# Schematic.net
KiCad netlist of a schematic drawn in EAGLE
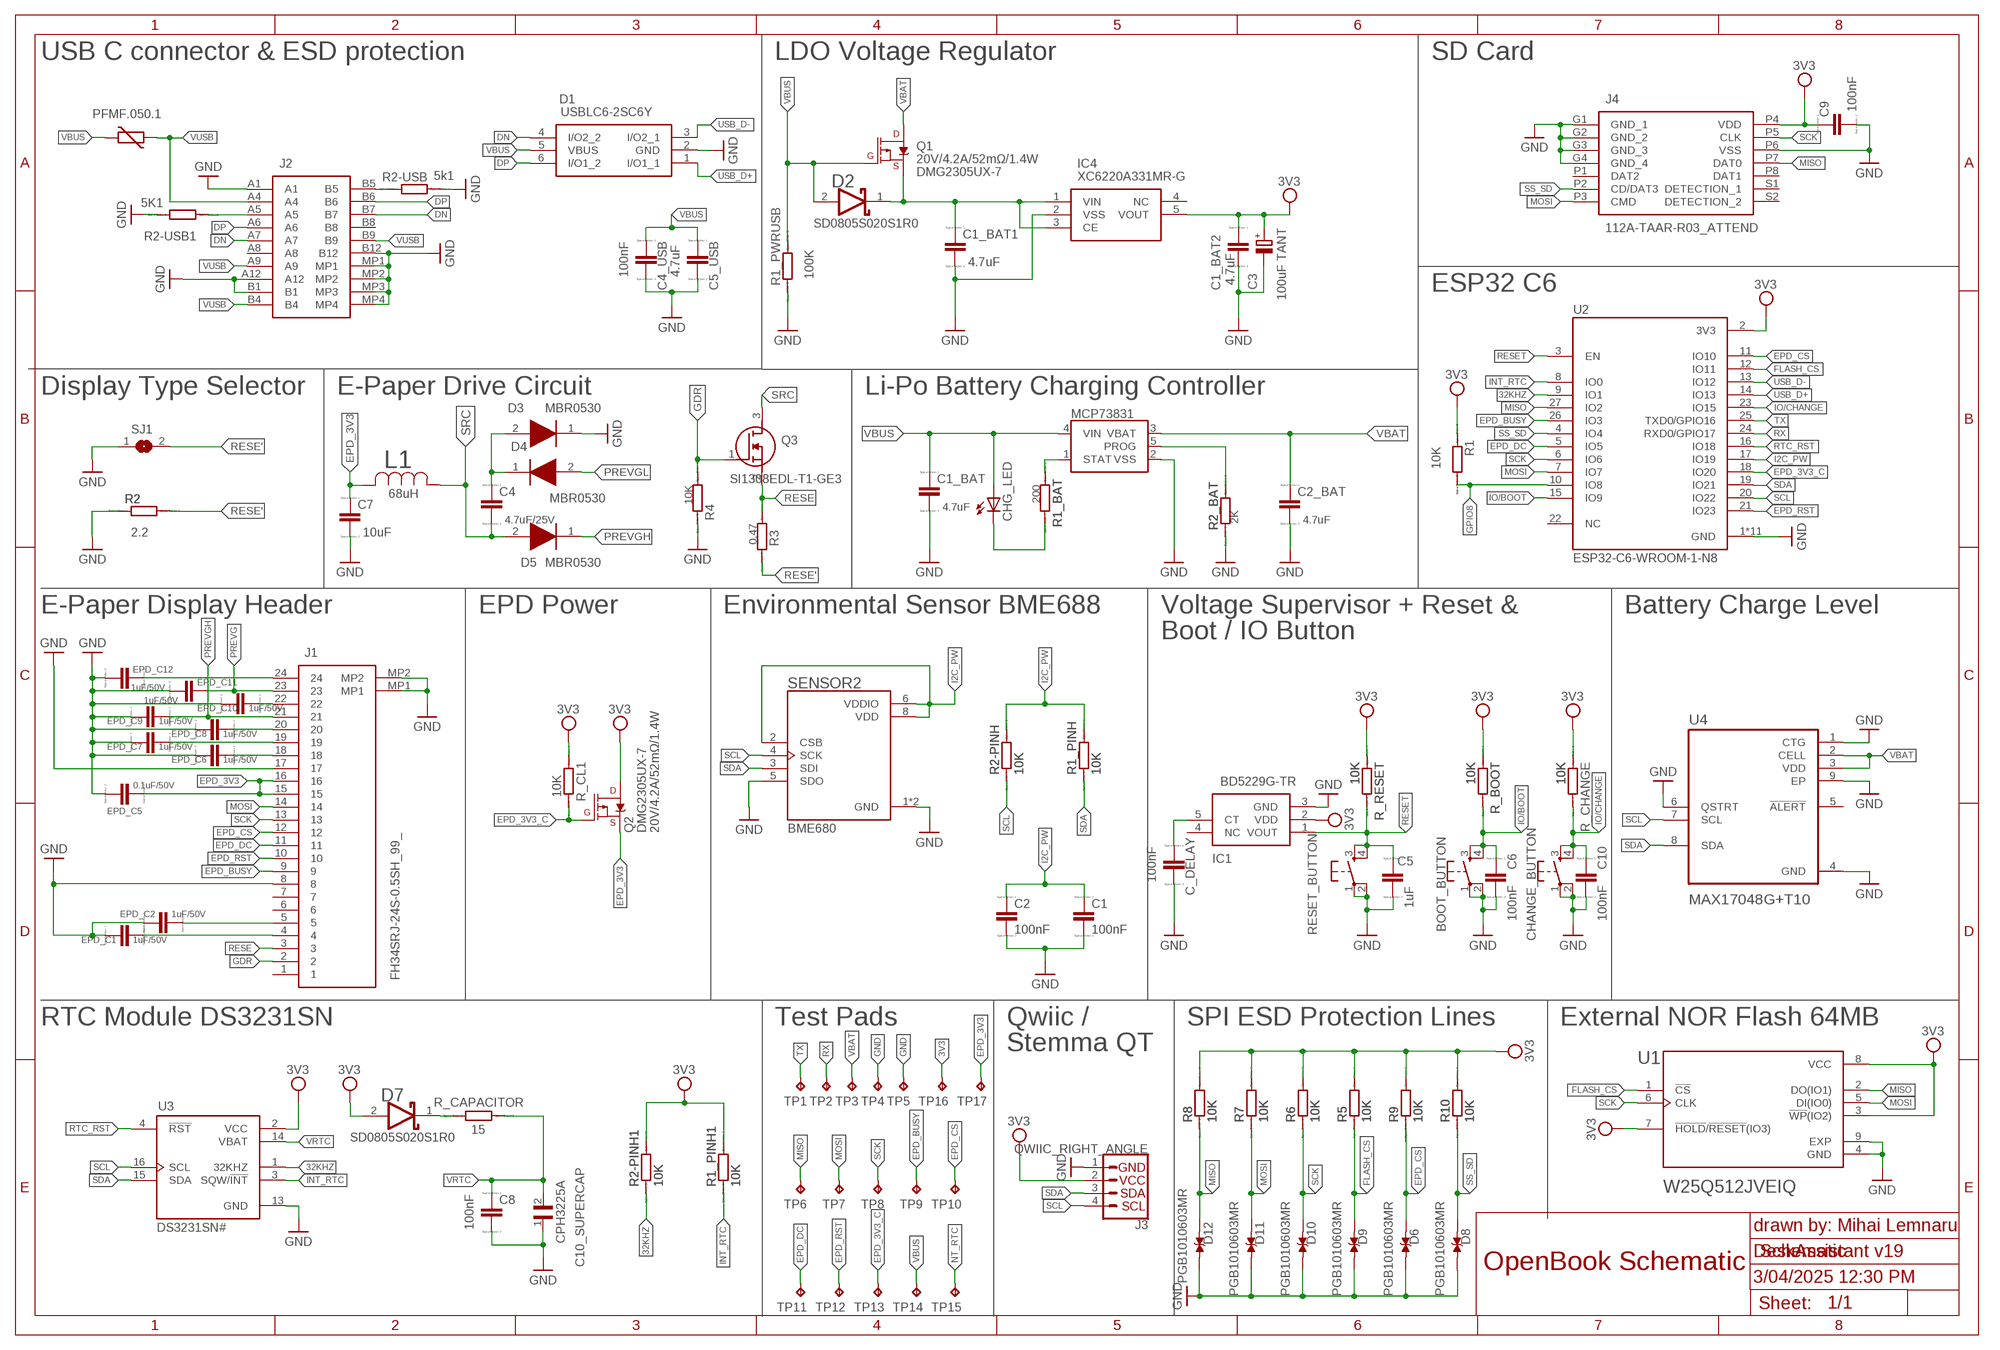
[diagram p0: schematic, sheet 1]

(export (version "E")
  (design (tool "Eeschema 10.0.6"))
  (components
    (comp (ref "5K1")
      (value "ESP32_WROVER_EAGLE-LTSPICE_RR0402")
      (footprint "eagle-import:ESP32_WROVER_EAGLE-LTSPICE_R0402")
      (libsource (lib "eagle-import") (part "ESP32_WROVER_EAGLE-LTSPICE_RR0402"))
    )
    (comp (ref "BOOT_BUTTON")
      (value "BUTTON_CUSYOMV1")
      (footprint "eagle-import:MYBUTTON")
      (libsource (lib "eagle-import") (part "BUTTON_CUSYOMV1"))
    )
    (comp (ref "C1")
      (value "100nF")
      (footprint "eagle-import:EAGLE-LTSPICE_C0402")
      (libsource (lib "eagle-import") (part "EAGLE-LTSPICE_CC0402"))
    )
    (comp (ref "C1_BAT")
      (value "EAGLE-LTSPICE_CC0402")
      (footprint "eagle-import:EAGLE-LTSPICE_C0402")
      (fields (field (name "C4_BAT") "4.7uF"))
      (libsource (lib "eagle-import") (part "EAGLE-LTSPICE_CC0402"))
    )
    (comp (ref "C1_BAT1")
      (value "EAGLE-LTSPICE_CC0402")
      (footprint "eagle-import:EAGLE-LTSPICE_C0402")
      (fields (field (name "C1_BAT1") "4.7uF"))
      (libsource (lib "eagle-import") (part "EAGLE-LTSPICE_CC0402"))
    )
    (comp (ref "C1_BAT2")
      (value "EAGLE-LTSPICE_CC0402")
      (footprint "eagle-import:EAGLE-LTSPICE_C0402")
      (fields (field (name "C1_BAT2") "4.7uF"))
      (libsource (lib "eagle-import") (part "EAGLE-LTSPICE_CC0402"))
    )
    (comp (ref "C2")
      (value "100nF")
      (footprint "eagle-import:EAGLE-LTSPICE_C0402")
      (libsource (lib "eagle-import") (part "EAGLE-LTSPICE_CC0402"))
    )
    (comp (ref "C2_BAT")
      (value "EAGLE-LTSPICE_CC0402")
      (footprint "eagle-import:EAGLE-LTSPICE_C0402")
      (fields (field (name "C2_BAT") "4.7uF"))
      (libsource (lib "eagle-import") (part "EAGLE-LTSPICE_CC0402"))
    )
    (comp (ref "C3")
      (value "RCL_CPOL-EUCT3528")
      (footprint "eagle-import:RCL_CT3528")
      (fields (field (name "C3") "100uF TANT"))
      (libsource (lib "eagle-import") (part "RCL_CPOL-EUCT3528"))
    )
    (comp (ref "C4")
      (value "ESP32_WROVER_EAGLE-LTSPICE_CC0402")
      (footprint "eagle-import:ESP32_WROVER_EAGLE-LTSPICE_C0402")
      (fields (field (name "C4") "4.7uF/25V"))
      (libsource (lib "eagle-import") (part "ESP32_WROVER_EAGLE-LTSPICE_CC0402"))
    )
    (comp (ref "C4_USB")
      (value "100nF")
      (footprint "eagle-import:EAGLE-LTSPICE_C0402")
      (fields (field (name "C4_USB") "100nF"))
      (libsource (lib "eagle-import") (part "EAGLE-LTSPICE_CC0402"))
    )
    (comp (ref "C5")
      (value "1uF")
      (footprint "eagle-import:EAGLE-LTSPICE_C0402")
      (libsource (lib "eagle-import") (part "EAGLE-LTSPICE_CC0402"))
    )
    (comp (ref "C5_USB")
      (value "4.7uF")
      (footprint "eagle-import:EAGLE-LTSPICE_C0402")
      (fields (field (name "C5_USB") "4.7uF"))
      (libsource (lib "eagle-import") (part "EAGLE-LTSPICE_CC0402"))
    )
    (comp (ref "C6")
      (value "100nF")
      (footprint "eagle-import:EAGLE-LTSPICE_C0402")
      (libsource (lib "eagle-import") (part "EAGLE-LTSPICE_CC0402"))
    )
    (comp (ref "C7")
      (value "ESP32_WROVER_EAGLE-LTSPICE_CC0402")
      (footprint "eagle-import:ESP32_WROVER_EAGLE-LTSPICE_C0402")
      (fields (field (name "C7") "10uF"))
      (libsource (lib "eagle-import") (part "ESP32_WROVER_EAGLE-LTSPICE_CC0402"))
    )
    (comp (ref "C8")
      (value "100nF")
      (footprint "eagle-import:EAGLE-LTSPICE_C0402")
      (libsource (lib "eagle-import") (part "EAGLE-LTSPICE_CC0402"))
    )
    (comp (ref "C9")
      (value "EAGLE-LTSPICE_CC0402")
      (footprint "eagle-import:EAGLE-LTSPICE_C0402")
      (fields (field (name "C9") "100nF"))
      (libsource (lib "eagle-import") (part "EAGLE-LTSPICE_CC0402"))
    )
    (comp (ref "C10")
      (value "100nF")
      (footprint "eagle-import:EAGLE-LTSPICE_C0402")
      (libsource (lib "eagle-import") (part "EAGLE-LTSPICE_CC0402"))
    )
    (comp (ref "C10_SUPERCAP")
      (value "CPH3225A")
      (footprint "eagle-import:CAPCP3225X100N")
      (fields (field (name "MF") "Seiko Instruments"))
      (libsource (lib "eagle-import") (part "CPH3225A"))
    )
    (comp (ref "CHANGE_BUTTON")
      (value "BUTTON_CUSYOMV1")
      (footprint "eagle-import:MYBUTTON")
      (libsource (lib "eagle-import") (part "BUTTON_CUSYOMV1"))
    )
    (comp (ref "CHG_LED")
      (value "ADAFRUIT_LEDCHIP-LED0603")
      (footprint "eagle-import:ADAFRUIT_CHIP-LED0603")
      (libsource (lib "eagle-import") (part "ADAFRUIT_LEDCHIP-LED0603"))
    )
    (comp (ref "C_DELAY")
      (value "100nF")
      (footprint "eagle-import:EAGLE-LTSPICE_C0402")
      (libsource (lib "eagle-import") (part "EAGLE-LTSPICE_CC0402"))
    )
    (comp (ref "D1")
      (value "USBLC6-2SC6Y")
      (footprint "eagle-import:SOT95P280X145-6N")
      (fields (field (name "MF") "STMicroelectronics"))
      (libsource (lib "eagle-import") (part "USBLC6-2SC6Y"))
    )
    (comp (ref "D2")
      (value "ESP32_WROVER_AVX---SD0805S020S1R0_AVX_SD0805S020S1R0_0_0AVX_SD0805S020S1R0_0_0")
      (footprint "eagle-import:ESP32_WROVER_AVX---SD0805S020S1R0_AVX_SD0805S020S1R0_0")
      (fields
        (field (name "DIGIKEY_PART_NUMBER") "478-7800-1-ND")
        (field (name "MF") "AVX")
        (field (name "MOUSER_PART_NUMBER") "581-SD0805S020S1R0")
      )
      (libsource (lib "eagle-import") (part "ESP32_WROVER_AVX---SD0805S020S1R0_AVX_SD0805S020S1R0_0_0AVX_SD0805S020S1R0_0_0"))
    )
    (comp (ref "D3")
      (value "MBR0530")
      (footprint "eagle-import:SOD3716X135N")
      (fields (field (name "MF") "ON Semiconductor"))
      (libsource (lib "eagle-import") (part "MBR0530"))
    )
    (comp (ref "D4")
      (value "MBR0530")
      (footprint "eagle-import:SOD3716X135N")
      (fields (field (name "MF") "ON Semiconductor"))
      (libsource (lib "eagle-import") (part "MBR0530"))
    )
    (comp (ref "D5")
      (value "MBR0530")
      (footprint "eagle-import:SOD3716X135N")
      (fields (field (name "MF") "ON Semiconductor"))
      (libsource (lib "eagle-import") (part "MBR0530"))
    )
    (comp (ref "D6")
      (value "PGB1010603MR")
      (footprint "eagle-import:DIOC1608X36N")
      (fields (field (name "MF") "Littelfuse Inc."))
      (libsource (lib "eagle-import") (part "PGB1010603MR"))
    )
    (comp (ref "D7")
      (value "ESP32_WROVER_AVX---SD0805S020S1R0_AVX_SD0805S020S1R0_0_0AVX_SD0805S020S1R0_0_0")
      (footprint "eagle-import:ESP32_WROVER_AVX---SD0805S020S1R0_AVX_SD0805S020S1R0_0")
      (fields
        (field (name "DIGIKEY_PART_NUMBER") "478-7800-1-ND")
        (field (name "MF") "AVX")
        (field (name "MOUSER_PART_NUMBER") "581-SD0805S020S1R0")
      )
      (libsource (lib "eagle-import") (part "ESP32_WROVER_AVX---SD0805S020S1R0_AVX_SD0805S020S1R0_0_0AVX_SD0805S020S1R0_0_0"))
    )
    (comp (ref "D8")
      (value "PGB1010603MR")
      (footprint "eagle-import:DIOC1608X36N")
      (fields (field (name "MF") "Littelfuse Inc."))
      (libsource (lib "eagle-import") (part "PGB1010603MR"))
    )
    (comp (ref "D9")
      (value "PGB1010603MR")
      (footprint "eagle-import:DIOC1608X36N")
      (fields (field (name "MF") "Littelfuse Inc."))
      (libsource (lib "eagle-import") (part "PGB1010603MR"))
    )
    (comp (ref "D10")
      (value "PGB1010603MR")
      (footprint "eagle-import:DIOC1608X36N")
      (fields (field (name "MF") "Littelfuse Inc."))
      (libsource (lib "eagle-import") (part "PGB1010603MR"))
    )
    (comp (ref "D11")
      (value "PGB1010603MR")
      (footprint "eagle-import:DIOC1608X36N")
      (fields (field (name "MF") "Littelfuse Inc."))
      (libsource (lib "eagle-import") (part "PGB1010603MR"))
    )
    (comp (ref "D12")
      (value "PGB1010603MR")
      (footprint "eagle-import:DIOC1608X36N")
      (fields (field (name "MF") "Littelfuse Inc."))
      (libsource (lib "eagle-import") (part "PGB1010603MR"))
    )
    (comp (ref "EPD_C1")
      (value "1uF/50V")
      (footprint "eagle-import:ESP32_WROVER_EAGLE-LTSPICE_C0402")
      (libsource (lib "eagle-import") (part "ESP32_WROVER_EAGLE-LTSPICE_CC0402"))
    )
    (comp (ref "EPD_C2")
      (value "1uF/50V")
      (footprint "eagle-import:ESP32_WROVER_EAGLE-LTSPICE_C0402")
      (libsource (lib "eagle-import") (part "ESP32_WROVER_EAGLE-LTSPICE_CC0402"))
    )
    (comp (ref "EPD_C5")
      (value "0.1uF/50V")
      (footprint "eagle-import:EAGLE-LTSPICE_C0402")
      (libsource (lib "eagle-import") (part "EAGLE-LTSPICE_CC0402"))
    )
    (comp (ref "EPD_C6")
      (value "1uF/50V")
      (footprint "eagle-import:EAGLE-LTSPICE_C0402")
      (libsource (lib "eagle-import") (part "EAGLE-LTSPICE_CC0402"))
    )
    (comp (ref "EPD_C7")
      (value "1uF/50V")
      (footprint "eagle-import:EAGLE-LTSPICE_C0402")
      (fields (field (name "EPD_C7") "1uF/50V"))
      (libsource (lib "eagle-import") (part "EAGLE-LTSPICE_CC0402"))
    )
    (comp (ref "EPD_C8")
      (value "1uF/50V")
      (footprint "eagle-import:EAGLE-LTSPICE_C0402")
      (fields (field (name "EPD_C8") "1uF/50V"))
      (libsource (lib "eagle-import") (part "EAGLE-LTSPICE_CC0402"))
    )
    (comp (ref "EPD_C9")
      (value "1uF/50V")
      (footprint "eagle-import:EAGLE-LTSPICE_C0402")
      (fields (field (name "EPD_C9") "1uF/50V"))
      (libsource (lib "eagle-import") (part "EAGLE-LTSPICE_CC0402"))
    )
    (comp (ref "EPD_C10")
      (value "1uF/50V")
      (footprint "eagle-import:EAGLE-LTSPICE_C0402")
      (fields (field (name "EPD_C10") "1uF/50V"))
      (libsource (lib "eagle-import") (part "EAGLE-LTSPICE_CC0402"))
    )
    (comp (ref "EPD_C11")
      (value "EAGLE-LTSPICE_CC0402")
      (footprint "eagle-import:EAGLE-LTSPICE_C0402")
      (fields (field (name "EPD_C11") "1uF/50V"))
      (libsource (lib "eagle-import") (part "EAGLE-LTSPICE_CC0402"))
    )
    (comp (ref "EPD_C12")
      (value "EAGLE-LTSPICE_CC0402")
      (footprint "eagle-import:EAGLE-LTSPICE_C0402")
      (fields (field (name "EPD_C12") "1uF/50V"))
      (libsource (lib "eagle-import") (part "EAGLE-LTSPICE_CC0402"))
    )
    (comp (ref "IC1")
      (value "BD5229G-TR")
      (footprint "eagle-import:SOT95P280X125-5N")
      (fields (field (name "MOUSER_PART_NUMBER") "755-BD5229G-TR"))
      (libsource (lib "eagle-import") (part "BD5229G-TR"))
    )
    (comp (ref "IC4")
      (value "XC6220A331MR-G")
      (footprint "eagle-import:SOT95P280X120-5N")
      (fields (field (name "MOUSER_PART_NUMBER") "865-XC6220A331MR-G"))
      (libsource (lib "eagle-import") (part "XC6220A331MR-G"))
    )
    (comp (ref "J1")
      (value "FH34SRJ-24S-0.5SH_99_")
      (footprint "eagle-import:FH34SRJ24S05SH99")
      (fields
        (field (name "MANUFACTURER_PART_NUMBER") "FH34SRJ-24S-0.5SH(99)")
        (field (name "MOUSER_PART_NUMBER") "798-FH34SRJ24S05SH99")
      )
      (libsource (lib "eagle-import") (part "FH34SRJ-24S-0.5SH_99_"))
    )
    (comp (ref "J2")
      (value "SAMACSYS_PARTS_USB4110-GF-A")
      (footprint "eagle-import:SAMACSYS_PARTS_USB4110GFA")
      (fields
        (field (name "MANUFACTURER_PART_NUMBER") "USB4110-GF-A")
        (field (name "MOUSER_PART_NUMBER") "640-USB4110-GF-A")
      )
      (libsource (lib "eagle-import") (part "SAMACSYS_PARTS_USB4110-GF-A"))
    )
    (comp (ref "J3")
      (value "QWIIC_RIGHT_ANGLE")
      (footprint "eagle-import:JST04_1MM_RA")
      (libsource (lib "eagle-import") (part "QWIIC_CONNECTORJS-1MM"))
    )
    (comp (ref "J4")
      (value "112A-TAAR-R03_ATTEND")
      (footprint "eagle-import:112ATAARR03ATTEND")
      (fields (field (name "MANUFACTURER_PART_NUMBER") "112A-TAAR-R03 ATTEND"))
      (libsource (lib "eagle-import") (part "112A-TAAR-R03_ATTEND"))
    )
    (comp (ref "L1")
      (value "744043680IND_4828-WE-TPC_WRE")
      (footprint "eagle-import:IND_4828-WE-TPC_WRE")
      (fields
        (field (name "MANUFACTURER_PART_NUMBER") "744043680")
        (field (name "L1") "68uH")
        (field (name "COPYRIGHT") "Copyright (C) 2024 Ultra Librarian. All rights reserved.")
      )
      (libsource (lib "eagle-import") (part "744043680IND_4828-WE-TPC_WRE"))
    )
    (comp (ref "MCP73831")
      (value "ESP32_WROVER_SPARKFUN-IC-POWER_MCP73831")
      (footprint "eagle-import:ESP32_WROVER_SPARKFUN-IC-POWER_SOT23-5")
      (libsource (lib "eagle-import") (part "ESP32_WROVER_SPARKFUN-IC-POWER_MCP73831"))
    )
    (comp (ref "PFMF.050.1")
      (value "ESP32C6_VARISTORCN1812")
      (footprint "eagle-import:ESP32C6_VARISTOR_CT_CN1812")
      (libsource (lib "eagle-import") (part "ESP32C6_VARISTORCN1812"))
    )
    (comp (ref "Q1")
      (value "20V/4.2A/52mΩ/1.4W")
      (footprint "eagle-import:ESP32_WROVER_SPARKFUN-DISCRETESEMI_SOT23-3")
      (libsource (lib "eagle-import") (part "ESP32_WROVER_SPARKFUN-DISCRETESEMI_MOSFET_PCH-DMG2305UX-7"))
    )
    (comp (ref "Q2")
      (value "20V/4.2A/52mΩ/1.4W")
      (footprint "eagle-import:ESP32_WROVER_SPARKFUN-DISCRETESEMI_SOT23-3")
      (libsource (lib "eagle-import") (part "ESP32_WROVER_SPARKFUN-DISCRETESEMI_MOSFET_PCH-DMG2305UX-7"))
    )
    (comp (ref "Q3")
      (value "SI1308EDL-T1-GE3")
      (footprint "eagle-import:SOT65P210X110-3N")
      (fields (field (name "MF") "Vishay Siliconix"))
      (libsource (lib "eagle-import") (part "SI1308EDL-T1-GE3"))
    )
    (comp (ref "R1")
      (value "ESP32_WROVER_EAGLE-LTSPICE_RR0402")
      (footprint "eagle-import:ESP32_WROVER_EAGLE-LTSPICE_R0402")
      (fields (field (name "R1") "10K"))
      (libsource (lib "eagle-import") (part "ESP32_WROVER_EAGLE-LTSPICE_RR0402"))
    )
    (comp (ref "R1_BAT")
      (value "ESP32_WROVER_EAGLE-LTSPICE_RR0402")
      (footprint "eagle-import:ESP32_WROVER_EAGLE-LTSPICE_R0402")
      (fields (field (name "R1_BAT") "200"))
      (libsource (lib "eagle-import") (part "ESP32_WROVER_EAGLE-LTSPICE_RR0402"))
    )
    (comp (ref "R1_PINH")
      (value "10K")
      (footprint "eagle-import:ESP32_WROVER_EAGLE-LTSPICE_R0402")
      (libsource (lib "eagle-import") (part "ESP32_WROVER_EAGLE-LTSPICE_RR0402"))
    )
    (comp (ref "R1_PINH1")
      (value "10K")
      (footprint "eagle-import:ESP32_WROVER_EAGLE-LTSPICE_R0402")
      (libsource (lib "eagle-import") (part "ESP32_WROVER_EAGLE-LTSPICE_RR0402"))
    )
    (comp (ref "R1_PWRUSB")
      (value "ESP32_WROVER_EAGLE-LTSPICE_RR0402")
      (footprint "eagle-import:ESP32_WROVER_EAGLE-LTSPICE_R0402")
      (fields (field (name "R1_PWRUSB") "100K"))
      (libsource (lib "eagle-import") (part "ESP32_WROVER_EAGLE-LTSPICE_RR0402"))
    )
    (comp (ref "R2")
      (value "ESP32_WROVER_EAGLE-LTSPICE_RR0402")
      (footprint "eagle-import:ESP32_WROVER_EAGLE-LTSPICE_R0402")
      (fields (field (name "R2") "2.2"))
      (libsource (lib "eagle-import") (part "ESP32_WROVER_EAGLE-LTSPICE_RR0402"))
    )
    (comp (ref "R2-PINH")
      (value "10K")
      (footprint "eagle-import:ESP32_WROVER_EAGLE-LTSPICE_R0402")
      (libsource (lib "eagle-import") (part "ESP32_WROVER_EAGLE-LTSPICE_RR0402"))
    )
    (comp (ref "R2-PINH1")
      (value "10K")
      (footprint "eagle-import:ESP32_WROVER_EAGLE-LTSPICE_R0402")
      (libsource (lib "eagle-import") (part "ESP32_WROVER_EAGLE-LTSPICE_RR0402"))
    )
    (comp (ref "R2-USB")
      (value "5k1")
      (footprint "eagle-import:ESP32_WROVER_EAGLE-LTSPICE_R0402")
      (libsource (lib "eagle-import") (part "ESP32_WROVER_EAGLE-LTSPICE_RR0402"))
    )
    (comp (ref "R2_BAT")
      (value "ESP32_WROVER_EAGLE-LTSPICE_RR0402")
      (footprint "eagle-import:ESP32_WROVER_EAGLE-LTSPICE_R0402")
      (fields (field (name "R2_BAT") "2K"))
      (libsource (lib "eagle-import") (part "ESP32_WROVER_EAGLE-LTSPICE_RR0402"))
    )
    (comp (ref "R3")
      (value "ESP32_WROVER_EAGLE-LTSPICE_RR0402")
      (footprint "eagle-import:ESP32_WROVER_EAGLE-LTSPICE_R0402")
      (fields (field (name "R3") "0.47"))
      (libsource (lib "eagle-import") (part "ESP32_WROVER_EAGLE-LTSPICE_RR0402"))
    )
    (comp (ref "R4")
      (value "ESP32_WROVER_EAGLE-LTSPICE_RR0402")
      (footprint "eagle-import:ESP32_WROVER_EAGLE-LTSPICE_R0402")
      (fields (field (name "R4") "10K"))
      (libsource (lib "eagle-import") (part "ESP32_WROVER_EAGLE-LTSPICE_RR0402"))
    )
    (comp (ref "R5")
      (value "10K")
      (footprint "eagle-import:ESP32_WROVER_EAGLE-LTSPICE_R0402")
      (libsource (lib "eagle-import") (part "ESP32_WROVER_EAGLE-LTSPICE_RR0402"))
    )
    (comp (ref "R6")
      (value "10K")
      (footprint "eagle-import:ESP32_WROVER_EAGLE-LTSPICE_R0402")
      (libsource (lib "eagle-import") (part "ESP32_WROVER_EAGLE-LTSPICE_RR0402"))
    )
    (comp (ref "R7")
      (value "10K")
      (footprint "eagle-import:ESP32_WROVER_EAGLE-LTSPICE_R0402")
      (libsource (lib "eagle-import") (part "ESP32_WROVER_EAGLE-LTSPICE_RR0402"))
    )
    (comp (ref "R8")
      (value "10K")
      (footprint "eagle-import:ESP32_WROVER_EAGLE-LTSPICE_R0402")
      (libsource (lib "eagle-import") (part "ESP32_WROVER_EAGLE-LTSPICE_RR0402"))
    )
    (comp (ref "R9")
      (value "10K")
      (footprint "eagle-import:ESP32_WROVER_EAGLE-LTSPICE_R0402")
      (libsource (lib "eagle-import") (part "ESP32_WROVER_EAGLE-LTSPICE_RR0402"))
    )
    (comp (ref "R10")
      (value "10K")
      (footprint "eagle-import:ESP32_WROVER_EAGLE-LTSPICE_R0402")
      (libsource (lib "eagle-import") (part "ESP32_WROVER_EAGLE-LTSPICE_RR0402"))
    )
    (comp (ref "RESET_BUTTON")
      (value "BUTTON_CUSYOMV1")
      (footprint "eagle-import:MYBUTTON")
      (libsource (lib "eagle-import") (part "BUTTON_CUSYOMV1"))
    )
    (comp (ref "R_BOOT")
      (value "10K")
      (footprint "eagle-import:ESP32_WROVER_EAGLE-LTSPICE_R0402")
      (libsource (lib "eagle-import") (part "ESP32_WROVER_EAGLE-LTSPICE_RR0402"))
    )
    (comp (ref "R_CAPACITOR")
      (value "15")
      (footprint "eagle-import:ESP32_WROVER_EAGLE-LTSPICE_R0402")
      (libsource (lib "eagle-import") (part "ESP32_WROVER_EAGLE-LTSPICE_RR0402"))
    )
    (comp (ref "R_CHANGE")
      (value "10K")
      (footprint "eagle-import:ESP32_WROVER_EAGLE-LTSPICE_R0402")
      (libsource (lib "eagle-import") (part "ESP32_WROVER_EAGLE-LTSPICE_RR0402"))
    )
    (comp (ref "R_CL1")
      (value "10K")
      (footprint "eagle-import:ESP32_WROVER_EAGLE-LTSPICE_R0402")
      (libsource (lib "eagle-import") (part "ESP32_WROVER_EAGLE-LTSPICE_RR0402"))
    )
    (comp (ref "R_RESET")
      (value "10K")
      (footprint "eagle-import:ESP32_WROVER_EAGLE-LTSPICE_R0402")
      (libsource (lib "eagle-import") (part "ESP32_WROVER_EAGLE-LTSPICE_RR0402"))
    )
    (comp (ref "SENSOR2")
      (value "ESP32_WROVER_BME680_BME680")
      (footprint "eagle-import:ESP32_WROVER_BME680_PSON80P300X300X100-8N")
      (fields (field (name "MF") "Bosch Sensortec") (field (name "MP") "BME680"))
      (libsource (lib "eagle-import") (part "ESP32_WROVER_BME680_BME680"))
    )
    (comp (ref "SJ1") (value "SJ") (footprint "eagle-import:SJ") (libsource (lib "eagle-import") (part "SJ")))
    (comp (ref "TP1")
      (value "TPTP20R")
      (footprint "eagle-import:TP20R")
      (libsource (lib "eagle-import") (part "TPTP20R"))
    )
    (comp (ref "TP2")
      (value "TPTP20R")
      (footprint "eagle-import:TP20R")
      (libsource (lib "eagle-import") (part "TPTP20R"))
    )
    (comp (ref "TP3")
      (value "TPTP20R")
      (footprint "eagle-import:TP20R")
      (libsource (lib "eagle-import") (part "TPTP20R"))
    )
    (comp (ref "TP4")
      (value "TPTP20R")
      (footprint "eagle-import:TP20R")
      (libsource (lib "eagle-import") (part "TPTP20R"))
    )
    (comp (ref "TP5")
      (value "TPTP20R")
      (footprint "eagle-import:TP20R")
      (libsource (lib "eagle-import") (part "TPTP20R"))
    )
    (comp (ref "TP6")
      (value "TPTP20R")
      (footprint "eagle-import:TP20R")
      (libsource (lib "eagle-import") (part "TPTP20R"))
    )
    (comp (ref "TP7")
      (value "TPTP20R")
      (footprint "eagle-import:TP20R")
      (libsource (lib "eagle-import") (part "TPTP20R"))
    )
    (comp (ref "TP8")
      (value "TPTP20R")
      (footprint "eagle-import:TP20R")
      (libsource (lib "eagle-import") (part "TPTP20R"))
    )
    (comp (ref "TP9")
      (value "TPTP20R")
      (footprint "eagle-import:TP20R")
      (libsource (lib "eagle-import") (part "TPTP20R"))
    )
    (comp (ref "TP10")
      (value "TPTP20R")
      (footprint "eagle-import:TP20R")
      (libsource (lib "eagle-import") (part "TPTP20R"))
    )
    (comp (ref "TP11")
      (value "TPTP20R")
      (footprint "eagle-import:TP20R")
      (libsource (lib "eagle-import") (part "TPTP20R"))
    )
    (comp (ref "TP12")
      (value "TPTP20R")
      (footprint "eagle-import:TP20R")
      (libsource (lib "eagle-import") (part "TPTP20R"))
    )
    (comp (ref "TP13")
      (value "TPTP20R")
      (footprint "eagle-import:TP20R")
      (libsource (lib "eagle-import") (part "TPTP20R"))
    )
    (comp (ref "TP14")
      (value "TPTP20R")
      (footprint "eagle-import:TP20R")
      (libsource (lib "eagle-import") (part "TPTP20R"))
    )
    (comp (ref "TP15")
      (value "TPTP20R")
      (footprint "eagle-import:TP20R")
      (libsource (lib "eagle-import") (part "TPTP20R"))
    )
    (comp (ref "TP16")
      (value "TPTP20R")
      (footprint "eagle-import:TP20R")
      (libsource (lib "eagle-import") (part "TPTP20R"))
    )
    (comp (ref "TP17")
      (value "TPTP20R")
      (footprint "eagle-import:TP20R")
      (libsource (lib "eagle-import") (part "TPTP20R"))
    )
    (comp (ref "U1")
      (value "W25Q512JVEIQ")
      (footprint "eagle-import:SON127P600X800X80-9N")
      (fields (field (name "MF") "Winbond Electronics"))
      (libsource (lib "eagle-import") (part "W25Q512JVEIQ"))
    )
    (comp (ref "U2")
      (value "ESP32-C6-WROOM-1-N8")
      (footprint "eagle-import:XCVR_ESP32-C6-WROOM-1-N8")
      (fields (field (name "MF") "Espressif Systems"))
      (libsource (lib "eagle-import") (part "ESP32-C6-WROOM-1-N8"))
    )
    (comp (ref "U3")
      (value "DS3231SN#")
      (footprint "eagle-import:SOIC127P1032X265-16N")
      (fields (field (name "MF") "Analog Devices"))
      (libsource (lib "eagle-import") (part "DS3231SN#"))
    )
    (comp (ref "U4")
      (value "MAX17048G+T10")
      (footprint "eagle-import:SON50P200X200X80-9N")
      (fields (field (name "MF") "Analog Devices"))
      (libsource (lib "eagle-import") (part "MAX17048G+T10"))
    )
  )
  (nets
    (net (code "1") (name "3V3") (class "Default")
      (node (ref "C1_BAT2") (pin "1") (pinfunction "1_1") (pintype "passive"))
      (node (ref "C3") (pin "+") (pinfunction "+_+") (pintype "passive"))
      (node (ref "C9") (pin "1") (pinfunction "1_1") (pintype "passive"))
      (node (ref "D7") (pin "2") (pinfunction "ANODE_2") (pintype "bidirectional"))
      (node (ref "IC1") (pin "2") (pinfunction "VDD_2") (pintype "bidirectional"))
      (node (ref "IC4") (pin "5") (pinfunction "VOUT_5") (pintype "bidirectional"))
      (node (ref "J3") (pin "2") (pinfunction "2_2") (pintype "power_in"))
      (node (ref "J4") (pin "P4") (pinfunction "VDD_P4") (pintype "bidirectional"))
      (node (ref "Q2") (pin "3") (pinfunction "D_3") (pintype "bidirectional"))
      (node (ref "R1") (pin "1") (pinfunction "1_1") (pintype "passive"))
      (node (ref "R10") (pin "2") (pinfunction "2_2") (pintype "passive"))
      (node (ref "R1_PINH1") (pin "2") (pinfunction "2_2") (pintype "passive"))
      (node (ref "R2-PINH1") (pin "2") (pinfunction "2_2") (pintype "passive"))
      (node (ref "R5") (pin "2") (pinfunction "2_2") (pintype "passive"))
      (node (ref "R6") (pin "2") (pinfunction "2_2") (pintype "passive"))
      (node (ref "R7") (pin "2") (pinfunction "2_2") (pintype "passive"))
      (node (ref "R8") (pin "2") (pinfunction "2_2") (pintype "passive"))
      (node (ref "R9") (pin "2") (pinfunction "2_2") (pintype "passive"))
      (node (ref "R_BOOT") (pin "1") (pinfunction "1_1") (pintype "passive"))
      (node (ref "R_CHANGE") (pin "1") (pinfunction "1_1") (pintype "passive"))
      (node (ref "R_CL1") (pin "1") (pinfunction "1_1") (pintype "passive"))
      (node (ref "R_RESET") (pin "1") (pinfunction "1_1") (pintype "passive"))
      (node (ref "TP16") (pin "TP") (pinfunction "TP_TP") (pintype "input"))
      (node (ref "U1") (pin "3") (pinfunction "~{WP}(IO2)_3") (pintype "bidirectional"))
      (node (ref "U1") (pin "7") (pinfunction "~{HOLD}/~{RESET}(IO3)_7") (pintype "bidirectional"))
      (node (ref "U1") (pin "8") (pinfunction "VCC_8") (pintype "power_in"))
      (node (ref "U2") (pin "2") (pinfunction "3V3_2") (pintype "power_in"))
      (node (ref "U3") (pin "2") (pinfunction "VCC_2") (pintype "power_in"))
    )
    (net (code "2") (name "32KHZ") (class "Default")
      (node (ref "R2-PINH1") (pin "1") (pinfunction "1_1") (pintype "passive"))
      (node (ref "U2") (pin "9") (pinfunction "IO1_9") (pintype "bidirectional"))
      (node (ref "U3") (pin "1") (pinfunction "32KHZ_1") (pintype "output"))
    )
    (net (code "3") (name "DN") (class "Default")
      (node (ref "D1") (pin "4") (pinfunction "I/O2_2_4") (pintype "bidirectional"))
      (node (ref "J2") (pin "A7") (pinfunction "A7_A7") (pintype "bidirectional"))
      (node (ref "J2") (pin "B7") (pinfunction "B7_B7") (pintype "bidirectional"))
    )
    (net (code "4") (name "DP") (class "Default")
      (node (ref "D1") (pin "6") (pinfunction "I/O1_2_6") (pintype "bidirectional"))
      (node (ref "J2") (pin "A6") (pinfunction "A6_A6") (pintype "bidirectional"))
      (node (ref "J2") (pin "B6") (pinfunction "B6_B6") (pintype "bidirectional"))
    )
    (net (code "5") (name "EPD_3V3") (class "Default")
      (node (ref "C7") (pin "1") (pinfunction "1_1") (pintype "passive"))
      (node (ref "EPD_C5") (pin "1") (pinfunction "1_1") (pintype "passive"))
      (node (ref "J1") (pin "15") (pinfunction "15_15") (pintype "bidirectional"))
      (node (ref "J1") (pin "16") (pinfunction "16_16") (pintype "bidirectional"))
      (node (ref "L1") (pin "2") (pinfunction "2_2") (pintype "passive"))
      (node (ref "Q2") (pin "2") (pinfunction "S_2") (pintype "bidirectional"))
      (node (ref "TP17") (pin "TP") (pinfunction "TP_TP") (pintype "input"))
    )
    (net (code "6") (name "EPD_3V3_C") (class "Default")
      (node (ref "Q2") (pin "1") (pinfunction "G_1") (pintype "bidirectional"))
      (node (ref "R_CL1") (pin "2") (pinfunction "2_2") (pintype "passive"))
      (node (ref "TP13") (pin "TP") (pinfunction "TP_TP") (pintype "input"))
      (node (ref "U2") (pin "18") (pinfunction "IO20_18") (pintype "bidirectional"))
    )
    (net (code "7") (name "EPD_BUSY") (class "Default")
      (node (ref "J1") (pin "9") (pinfunction "9_9") (pintype "bidirectional"))
      (node (ref "TP9") (pin "TP") (pinfunction "TP_TP") (pintype "input"))
      (node (ref "U2") (pin "26") (pinfunction "IO3_26") (pintype "bidirectional"))
    )
    (net (code "8") (name "EPD_CS") (class "Default")
      (node (ref "D6") (pin "2") (pinfunction "2_2") (pintype "passive"))
      (node (ref "J1") (pin "12") (pinfunction "12_12") (pintype "bidirectional"))
      (node (ref "R9") (pin "1") (pinfunction "1_1") (pintype "passive"))
      (node (ref "TP10") (pin "TP") (pinfunction "TP_TP") (pintype "input"))
      (node (ref "U2") (pin "11") (pinfunction "IO10_11") (pintype "bidirectional"))
    )
    (net (code "9") (name "EPD_DC") (class "Default")
      (node (ref "J1") (pin "11") (pinfunction "11_11") (pintype "bidirectional"))
      (node (ref "TP11") (pin "TP") (pinfunction "TP_TP") (pintype "input"))
      (node (ref "U2") (pin "5") (pinfunction "IO5_5") (pintype "bidirectional"))
    )
    (net (code "10") (name "EPD_RST") (class "Default")
      (node (ref "J1") (pin "10") (pinfunction "10_10") (pintype "bidirectional"))
      (node (ref "TP12") (pin "TP") (pinfunction "TP_TP") (pintype "input"))
      (node (ref "U2") (pin "21") (pinfunction "IO23_21") (pintype "bidirectional"))
    )
    (net (code "11") (name "FLASH_CS") (class "Default")
      (node (ref "D9") (pin "2") (pinfunction "2_2") (pintype "passive"))
      (node (ref "R5") (pin "1") (pinfunction "1_1") (pintype "passive"))
      (node (ref "U1") (pin "1") (pinfunction "~{CS}_1") (pintype "input"))
      (node (ref "U2") (pin "12") (pinfunction "IO11_12") (pintype "bidirectional"))
    )
    (net (code "12") (name "GDR") (class "Default")
      (node (ref "J1") (pin "2") (pinfunction "2_2") (pintype "bidirectional"))
      (node (ref "Q3") (pin "1") (pinfunction "G_1") (pintype "bidirectional"))
      (node (ref "R4") (pin "1") (pinfunction "1_1") (pintype "passive"))
    )
    (net (code "13") (name "GND") (class "Default")
      (node (ref "5K1") (pin "1") (pinfunction "1_1") (pintype "passive"))
      (node (ref "BOOT_BUTTON") (pin "1") (pinfunction "1_1") (pintype "passive"))
      (node (ref "BOOT_BUTTON") (pin "2") (pinfunction "2_2") (pintype "passive"))
      (node (ref "C1") (pin "2") (pinfunction "2_2") (pintype "passive"))
      (node (ref "C10") (pin "2") (pinfunction "2_2") (pintype "passive"))
      (node (ref "C10_SUPERCAP") (pin "1") (pinfunction "1_1") (pintype "passive"))
      (node (ref "C1_BAT") (pin "2") (pinfunction "2_2") (pintype "passive"))
      (node (ref "C1_BAT1") (pin "2") (pinfunction "2_2") (pintype "passive"))
      (node (ref "C1_BAT2") (pin "2") (pinfunction "2_2") (pintype "passive"))
      (node (ref "C2") (pin "2") (pinfunction "2_2") (pintype "passive"))
      (node (ref "C2_BAT") (pin "2") (pinfunction "2_2") (pintype "passive"))
      (node (ref "C3") (pin "-") (pinfunction "-_-") (pintype "passive"))
      (node (ref "C4_USB") (pin "2") (pinfunction "2_2") (pintype "passive"))
      (node (ref "C5") (pin "2") (pinfunction "2_2") (pintype "passive"))
      (node (ref "C5_USB") (pin "2") (pinfunction "2_2") (pintype "passive"))
      (node (ref "C6") (pin "2") (pinfunction "2_2") (pintype "passive"))
      (node (ref "C7") (pin "2") (pinfunction "2_2") (pintype "passive"))
      (node (ref "C8") (pin "2") (pinfunction "2_2") (pintype "passive"))
      (node (ref "C9") (pin "2") (pinfunction "2_2") (pintype "passive"))
      (node (ref "CHANGE_BUTTON") (pin "1") (pinfunction "1_1") (pintype "passive"))
      (node (ref "CHANGE_BUTTON") (pin "2") (pinfunction "2_2") (pintype "passive"))
      (node (ref "C_DELAY") (pin "2") (pinfunction "2_2") (pintype "passive"))
      (node (ref "D1") (pin "2") (pinfunction "GND_2") (pintype "bidirectional"))
      (node (ref "D10") (pin "1") (pinfunction "1_1") (pintype "passive"))
      (node (ref "D11") (pin "1") (pinfunction "1_1") (pintype "passive"))
      (node (ref "D12") (pin "1") (pinfunction "1_1") (pintype "passive"))
      (node (ref "D3") (pin "1") (pinfunction "K_1") (pintype "bidirectional"))
      (node (ref "D6") (pin "1") (pinfunction "1_1") (pintype "passive"))
      (node (ref "D8") (pin "1") (pinfunction "1_1") (pintype "passive"))
      (node (ref "D9") (pin "1") (pinfunction "1_1") (pintype "passive"))
      (node (ref "EPD_C1") (pin "2") (pinfunction "2_2") (pintype "passive"))
      (node (ref "EPD_C10") (pin "2") (pinfunction "2_2") (pintype "passive"))
      (node (ref "EPD_C11") (pin "2") (pinfunction "2_2") (pintype "passive"))
      (node (ref "EPD_C12") (pin "2") (pinfunction "2_2") (pintype "passive"))
      (node (ref "EPD_C2") (pin "2") (pinfunction "2_2") (pintype "passive"))
      (node (ref "EPD_C5") (pin "2") (pinfunction "2_2") (pintype "passive"))
      (node (ref "EPD_C6") (pin "2") (pinfunction "2_2") (pintype "passive"))
      (node (ref "EPD_C7") (pin "2") (pinfunction "2_2") (pintype "passive"))
      (node (ref "EPD_C8") (pin "2") (pinfunction "2_2") (pintype "passive"))
      (node (ref "EPD_C9") (pin "2") (pinfunction "2_2") (pintype "passive"))
      (node (ref "IC1") (pin "3") (pinfunction "GND_3") (pintype "bidirectional"))
      (node (ref "IC4") (pin "2") (pinfunction "VSS_2") (pintype "bidirectional"))
      (node (ref "J1") (pin "17") (pinfunction "17_17") (pintype "bidirectional"))
      (node (ref "J1") (pin "8") (pinfunction "8_8") (pintype "bidirectional"))
      (node (ref "J1") (pin "MP1") (pinfunction "MP1_MP1") (pintype "bidirectional"))
      (node (ref "J1") (pin "MP2") (pinfunction "MP2_MP2") (pintype "bidirectional"))
      (node (ref "J2") (pin "A1") (pinfunction "A1_A1") (pintype "bidirectional"))
      (node (ref "J2") (pin "A12") (pinfunction "A12_A12") (pintype "bidirectional"))
      (node (ref "J2") (pin "B1") (pinfunction "B1_B1") (pintype "bidirectional"))
      (node (ref "J2") (pin "B12") (pinfunction "B12_B12") (pintype "bidirectional"))
      (node (ref "J2") (pin "MP1") (pinfunction "MP1_MP1") (pintype "bidirectional"))
      (node (ref "J2") (pin "MP2") (pinfunction "MP2_MP2") (pintype "bidirectional"))
      (node (ref "J2") (pin "MP3") (pinfunction "MP3_MP3") (pintype "bidirectional"))
      (node (ref "J2") (pin "MP4") (pinfunction "MP4_MP4") (pintype "bidirectional"))
      (node (ref "J3") (pin "1") (pinfunction "1_1") (pintype "power_in"))
      (node (ref "J4") (pin "G1") (pinfunction "GND_1_G1") (pintype "bidirectional"))
      (node (ref "J4") (pin "G2") (pinfunction "GND_2_G2") (pintype "bidirectional"))
      (node (ref "J4") (pin "G3") (pinfunction "GND_3_G3") (pintype "bidirectional"))
      (node (ref "J4") (pin "G4") (pinfunction "GND_4_G4") (pintype "bidirectional"))
      (node (ref "J4") (pin "P6") (pinfunction "VSS_P6") (pintype "bidirectional"))
      (node (ref "MCP73831") (pin "2") (pinfunction "VSS_2") (pintype "power_in"))
      (node (ref "R1_PWRUSB") (pin "1") (pinfunction "1_1") (pintype "passive"))
      (node (ref "R2") (pin "1") (pinfunction "1_1") (pintype "passive"))
      (node (ref "R2-USB") (pin "2") (pinfunction "2_2") (pintype "passive"))
      (node (ref "R2_BAT") (pin "1") (pinfunction "1_1") (pintype "passive"))
      (node (ref "R4") (pin "2") (pinfunction "2_2") (pintype "passive"))
      (node (ref "RESET_BUTTON") (pin "1") (pinfunction "1_1") (pintype "passive"))
      (node (ref "RESET_BUTTON") (pin "2") (pinfunction "2_2") (pintype "passive"))
      (node (ref "SENSOR2") (pin "1") (pinfunction "GND_1") (pintype "power_in"))
      (node (ref "SENSOR2") (pin "5") (pinfunction "SDO_5") (pintype "bidirectional"))
      (node (ref "SENSOR2") (pin "7") (pinfunction "GND_7") (pintype "power_in"))
      (node (ref "SJ1") (pin "1") (pinfunction "1_1") (pintype "passive"))
      (node (ref "TP4") (pin "TP") (pinfunction "TP_TP") (pintype "input"))
      (node (ref "TP5") (pin "TP") (pinfunction "TP_TP") (pintype "input"))
      (node (ref "U1") (pin "4") (pinfunction "GND_4") (pintype "power_in"))
      (node (ref "U1") (pin "9") (pinfunction "EXP_9") (pintype "passive"))
      (node (ref "U2") (pin "1") (pinfunction "GND_1") (pintype "power_in"))
      (node (ref "U2") (pin "28") (pinfunction "GND_28") (pintype "power_in"))
      (node (ref "U2") (pin "29_1") (pinfunction "GND_29_1") (pintype "power_in"))
      (node (ref "U2") (pin "29_2") (pinfunction "GND_29_2") (pintype "power_in"))
      (node (ref "U2") (pin "29_3") (pinfunction "GND_29_3") (pintype "power_in"))
      (node (ref "U2") (pin "29_4") (pinfunction "GND_29_4") (pintype "power_in"))
      (node (ref "U2") (pin "29_5") (pinfunction "GND_29_5") (pintype "power_in"))
      (node (ref "U2") (pin "29_6") (pinfunction "GND_29_6") (pintype "power_in"))
      (node (ref "U2") (pin "29_7") (pinfunction "GND_29_7") (pintype "power_in"))
      (node (ref "U2") (pin "29_8") (pinfunction "GND_29_8") (pintype "power_in"))
      (node (ref "U2") (pin "29_9") (pinfunction "GND_29_9") (pintype "power_in"))
      (node (ref "U3") (pin "13") (pinfunction "GND_13") (pintype "power_in"))
      (node (ref "U4") (pin "1") (pinfunction "CTG_1") (pintype "power_in"))
      (node (ref "U4") (pin "4") (pinfunction "GND_4") (pintype "power_in"))
      (node (ref "U4") (pin "6") (pinfunction "QSTRT_6") (pintype "input"))
      (node (ref "U4") (pin "9") (pinfunction "EP_9") (pintype "power_in"))
    )
    (net (code "14") (name "GPIO8") (class "Default")
      (node (ref "R1") (pin "2") (pinfunction "2_2") (pintype "passive"))
      (node (ref "U2") (pin "10") (pinfunction "IO8_10") (pintype "bidirectional"))
    )
    (net (code "15") (name "I2C_PW") (class "Default")
      (node (ref "C1") (pin "1") (pinfunction "1_1") (pintype "passive"))
      (node (ref "C2") (pin "1") (pinfunction "1_1") (pintype "passive"))
      (node (ref "R1_PINH") (pin "2") (pinfunction "2_2") (pintype "passive"))
      (node (ref "R2-PINH") (pin "2") (pinfunction "2_2") (pintype "passive"))
      (node (ref "SENSOR2") (pin "2") (pinfunction "CSB_2") (pintype "input"))
      (node (ref "SENSOR2") (pin "6") (pinfunction "VDDIO_6") (pintype "power_in"))
      (node (ref "SENSOR2") (pin "8") (pinfunction "VDD_8") (pintype "power_in"))
      (node (ref "U2") (pin "17") (pinfunction "IO19_17") (pintype "bidirectional"))
    )
    (net (code "16") (name "INT_RTC") (class "Default")
      (node (ref "R1_PINH1") (pin "1") (pinfunction "1_1") (pintype "passive"))
      (node (ref "U2") (pin "8") (pinfunction "IO0_8") (pintype "bidirectional"))
      (node (ref "U3") (pin "3") (pinfunction "SQW/~{INT}_3") (pintype "output"))
    )
    (net (code "17") (name "IO{slash}BOOT") (class "Default")
      (node (ref "BOOT_BUTTON") (pin "3") (pinfunction "3_3") (pintype "passive"))
      (node (ref "BOOT_BUTTON") (pin "4") (pinfunction "4_4") (pintype "passive"))
      (node (ref "C6") (pin "1") (pinfunction "1_1") (pintype "passive"))
      (node (ref "R_BOOT") (pin "2") (pinfunction "2_2") (pintype "passive"))
      (node (ref "U2") (pin "15") (pinfunction "IO9_15") (pintype "bidirectional"))
    )
    (net (code "18") (name "IO{slash}CHANGE") (class "Default")
      (node (ref "C10") (pin "1") (pinfunction "1_1") (pintype "passive"))
      (node (ref "CHANGE_BUTTON") (pin "3") (pinfunction "3_3") (pintype "passive"))
      (node (ref "CHANGE_BUTTON") (pin "4") (pinfunction "4_4") (pintype "passive"))
      (node (ref "R_CHANGE") (pin "2") (pinfunction "2_2") (pintype "passive"))
      (node (ref "U2") (pin "23") (pinfunction "IO15_23") (pintype "bidirectional"))
    )
    (net (code "19") (name "MISO") (class "Default")
      (node (ref "D12") (pin "2") (pinfunction "2_2") (pintype "passive"))
      (node (ref "J4") (pin "P7") (pinfunction "DAT0_P7") (pintype "bidirectional"))
      (node (ref "R8") (pin "1") (pinfunction "1_1") (pintype "passive"))
      (node (ref "TP6") (pin "TP") (pinfunction "TP_TP") (pintype "input"))
      (node (ref "U1") (pin "2") (pinfunction "DO(IO1)_2") (pintype "bidirectional"))
      (node (ref "U2") (pin "27") (pinfunction "IO2_27") (pintype "bidirectional"))
    )
    (net (code "20") (name "MOSI") (class "Default")
      (node (ref "D11") (pin "2") (pinfunction "2_2") (pintype "passive"))
      (node (ref "J1") (pin "14") (pinfunction "14_14") (pintype "bidirectional"))
      (node (ref "J4") (pin "P3") (pinfunction "CMD_P3") (pintype "bidirectional"))
      (node (ref "R7") (pin "1") (pinfunction "1_1") (pintype "passive"))
      (node (ref "TP7") (pin "TP") (pinfunction "TP_TP") (pintype "input"))
      (node (ref "U1") (pin "5") (pinfunction "DI(IO0)_5") (pintype "bidirectional"))
      (node (ref "U2") (pin "7") (pinfunction "IO7_7") (pintype "bidirectional"))
    )
    (net (code "21") (name "NT_RTC") (class "Default")
      (node (ref "TP15") (pin "TP") (pinfunction "TP_TP") (pintype "input"))
    )
    (net (code "22") (name "Net-(5K1-Pad2)") (class "Default")
      (node (ref "5K1") (pin "2") (pinfunction "2_2") (pintype "passive"))
      (node (ref "J2") (pin "A5") (pinfunction "A5_A5") (pintype "bidirectional"))
    )
    (net (code "23") (name "Net-(CHG_LED-PadC)") (class "Default")
      (node (ref "CHG_LED") (pin "C") (pinfunction "C_C") (pintype "passive"))
      (node (ref "R1_BAT") (pin "2") (pinfunction "2_2") (pintype "passive"))
    )
    (net (code "24") (name "Net-(D2-CATHODE)") (class "Default")
      (node (ref "C1_BAT1") (pin "1") (pinfunction "1_1") (pintype "passive"))
      (node (ref "D2") (pin "1") (pinfunction "CATHODE_1") (pintype "bidirectional"))
      (node (ref "IC4") (pin "1") (pinfunction "VIN_1") (pintype "bidirectional"))
      (node (ref "IC4") (pin "3") (pinfunction "CE_3") (pintype "bidirectional"))
      (node (ref "Q1") (pin "2") (pinfunction "S_2") (pintype "bidirectional"))
    )
    (net (code "25") (name "Net-(D3-A)") (class "Default")
      (node (ref "C4") (pin "1") (pinfunction "1_1") (pintype "passive"))
      (node (ref "D3") (pin "2") (pinfunction "A_2") (pintype "bidirectional"))
      (node (ref "D4") (pin "1") (pinfunction "K_1") (pintype "bidirectional"))
    )
    (net (code "26") (name "Net-(D7-CATHODE)") (class "Default")
      (node (ref "D7") (pin "1") (pinfunction "CATHODE_1") (pintype "bidirectional"))
      (node (ref "R_CAPACITOR") (pin "2") (pinfunction "2_2") (pintype "passive"))
    )
    (net (code "27") (name "Net-(EPD_C1-Pad1)") (class "Default")
      (node (ref "EPD_C1") (pin "1") (pinfunction "1_1") (pintype "passive"))
      (node (ref "J1") (pin "4") (pinfunction "4_4") (pintype "bidirectional"))
    )
    (net (code "28") (name "Net-(EPD_C2-Pad1)") (class "Default")
      (node (ref "EPD_C2") (pin "1") (pinfunction "1_1") (pintype "passive"))
      (node (ref "J1") (pin "5") (pinfunction "5_5") (pintype "bidirectional"))
    )
    (net (code "29") (name "Net-(EPD_C6-Pad1)") (class "Default")
      (node (ref "EPD_C6") (pin "1") (pinfunction "1_1") (pintype "passive"))
      (node (ref "J1") (pin "18") (pinfunction "18_18") (pintype "bidirectional"))
    )
    (net (code "30") (name "Net-(EPD_C7-Pad1)") (class "Default")
      (node (ref "EPD_C7") (pin "1") (pinfunction "1_1") (pintype "passive"))
      (node (ref "J1") (pin "19") (pinfunction "19_19") (pintype "bidirectional"))
    )
    (net (code "31") (name "Net-(EPD_C8-Pad1)") (class "Default")
      (node (ref "EPD_C8") (pin "1") (pinfunction "1_1") (pintype "passive"))
      (node (ref "J1") (pin "20") (pinfunction "20_20") (pintype "bidirectional"))
    )
    (net (code "32") (name "Net-(EPD_C10-Pad1)") (class "Default")
      (node (ref "EPD_C10") (pin "1") (pinfunction "1_1") (pintype "passive"))
      (node (ref "J1") (pin "22") (pinfunction "22_22") (pintype "bidirectional"))
    )
    (net (code "33") (name "Net-(EPD_C12-Pad1)") (class "Default")
      (node (ref "EPD_C12") (pin "1") (pinfunction "1_1") (pintype "passive"))
      (node (ref "J1") (pin "24") (pinfunction "24_24") (pintype "bidirectional"))
    )
    (net (code "34") (name "Net-(IC1-CT)") (class "Default")
      (node (ref "C_DELAY") (pin "1") (pinfunction "1_1") (pintype "passive"))
      (node (ref "IC1") (pin "5") (pinfunction "CT_5") (pintype "bidirectional"))
    )
    (net (code "35") (name "Net-(J2-PadB5)") (class "Default")
      (node (ref "J2") (pin "B5") (pinfunction "B5_B5") (pintype "bidirectional"))
      (node (ref "R2-USB") (pin "1") (pinfunction "1_1") (pintype "passive"))
    )
    (net (code "36") (name "Net-(MCP73831-PROG)") (class "Default")
      (node (ref "MCP73831") (pin "5") (pinfunction "PROG_5") (pintype "input"))
      (node (ref "R2_BAT") (pin "2") (pinfunction "2_2") (pintype "passive"))
    )
    (net (code "37") (name "Net-(MCP73831-STAT)") (class "Default")
      (node (ref "MCP73831") (pin "1") (pinfunction "STAT_1") (pintype "output"))
      (node (ref "R1_BAT") (pin "1") (pinfunction "1_1") (pintype "passive"))
    )
    (net (code "38") (name "PREVG") (class "Default")
      (node (ref "EPD_C11") (pin "1") (pinfunction "1_1") (pintype "passive"))
      (node (ref "J1") (pin "23") (pinfunction "23_23") (pintype "bidirectional"))
    )
    (net (code "39") (name "PREVGH") (class "Default")
      (node (ref "D5") (pin "1") (pinfunction "K_1") (pintype "bidirectional"))
      (node (ref "EPD_C9") (pin "1") (pinfunction "1_1") (pintype "passive"))
      (node (ref "J1") (pin "21") (pinfunction "21_21") (pintype "bidirectional"))
    )
    (net (code "40") (name "PREVGL") (class "Default")
      (node (ref "D4") (pin "2") (pinfunction "A_2") (pintype "bidirectional"))
    )
    (net (code "41") (name "RESE") (class "Default")
      (node (ref "J1") (pin "3") (pinfunction "3_3") (pintype "bidirectional"))
      (node (ref "Q3") (pin "2") (pinfunction "S_2") (pintype "bidirectional"))
      (node (ref "R3") (pin "1") (pinfunction "1_1") (pintype "passive"))
    )
    (net (code "42") (name "RESE'") (class "Default")
      (node (ref "R2") (pin "2") (pinfunction "2_2") (pintype "passive"))
      (node (ref "R3") (pin "2") (pinfunction "2_2") (pintype "passive"))
      (node (ref "SJ1") (pin "2") (pinfunction "2_2") (pintype "passive"))
    )
    (net (code "43") (name "RESET") (class "Default")
      (node (ref "C5") (pin "1") (pinfunction "1_1") (pintype "passive"))
      (node (ref "IC1") (pin "1") (pinfunction "VOUT_1") (pintype "bidirectional"))
      (node (ref "RESET_BUTTON") (pin "3") (pinfunction "3_3") (pintype "passive"))
      (node (ref "RESET_BUTTON") (pin "4") (pinfunction "4_4") (pintype "passive"))
      (node (ref "R_RESET") (pin "2") (pinfunction "2_2") (pintype "passive"))
      (node (ref "U2") (pin "3") (pinfunction "EN_3") (pintype "input"))
    )
    (net (code "44") (name "RTC_RST") (class "Default")
      (node (ref "U2") (pin "16") (pinfunction "IO18_16") (pintype "bidirectional"))
      (node (ref "U3") (pin "4") (pinfunction "~{RST}_4") (pintype "input"))
    )
    (net (code "45") (name "RX") (class "Default")
      (node (ref "TP2") (pin "TP") (pinfunction "TP_TP") (pintype "input"))
      (node (ref "U2") (pin "24") (pinfunction "RXD0/GPIO17_24") (pintype "bidirectional"))
    )
    (net (code "46") (name "SCK") (class "Default")
      (node (ref "D10") (pin "2") (pinfunction "2_2") (pintype "passive"))
      (node (ref "J1") (pin "13") (pinfunction "13_13") (pintype "bidirectional"))
      (node (ref "J4") (pin "P5") (pinfunction "CLK_P5") (pintype "bidirectional"))
      (node (ref "R6") (pin "1") (pinfunction "1_1") (pintype "passive"))
      (node (ref "TP8") (pin "TP") (pinfunction "TP_TP") (pintype "input"))
      (node (ref "U1") (pin "6") (pinfunction "CLK_6") (pintype "input"))
      (node (ref "U2") (pin "6") (pinfunction "IO6_6") (pintype "bidirectional"))
    )
    (net (code "47") (name "SCL") (class "Default")
      (node (ref "J3") (pin "4") (pinfunction "4_4") (pintype "passive"))
      (node (ref "R2-PINH") (pin "1") (pinfunction "1_1") (pintype "passive"))
      (node (ref "SENSOR2") (pin "4") (pinfunction "SCK_4") (pintype "input"))
      (node (ref "U2") (pin "20") (pinfunction "IO22_20") (pintype "bidirectional"))
      (node (ref "U3") (pin "16") (pinfunction "SCL_16") (pintype "input"))
      (node (ref "U4") (pin "7") (pinfunction "SCL_7") (pintype "input"))
    )
    (net (code "48") (name "SDA") (class "Default")
      (node (ref "J3") (pin "3") (pinfunction "3_3") (pintype "passive"))
      (node (ref "R1_PINH") (pin "1") (pinfunction "1_1") (pintype "passive"))
      (node (ref "SENSOR2") (pin "3") (pinfunction "SDI_3") (pintype "bidirectional"))
      (node (ref "U2") (pin "19") (pinfunction "IO21_19") (pintype "bidirectional"))
      (node (ref "U3") (pin "15") (pinfunction "SDA_15") (pintype "bidirectional"))
      (node (ref "U4") (pin "8") (pinfunction "SDA_8") (pintype "bidirectional"))
    )
    (net (code "49") (name "SRC") (class "Default")
      (node (ref "C4") (pin "2") (pinfunction "2_2") (pintype "passive"))
      (node (ref "D5") (pin "2") (pinfunction "A_2") (pintype "bidirectional"))
      (node (ref "L1") (pin "1") (pinfunction "1_1") (pintype "passive"))
      (node (ref "Q3") (pin "3") (pinfunction "D_3") (pintype "bidirectional"))
    )
    (net (code "50") (name "SS_SD") (class "Default")
      (node (ref "D8") (pin "2") (pinfunction "2_2") (pintype "passive"))
      (node (ref "J4") (pin "P2") (pinfunction "CD/DAT3_P2") (pintype "bidirectional"))
      (node (ref "R10") (pin "1") (pinfunction "1_1") (pintype "passive"))
      (node (ref "U2") (pin "4") (pinfunction "IO4_4") (pintype "bidirectional"))
    )
    (net (code "51") (name "TX") (class "Default")
      (node (ref "TP1") (pin "TP") (pinfunction "TP_TP") (pintype "input"))
      (node (ref "U2") (pin "25") (pinfunction "TXD0/GPIO16_25") (pintype "bidirectional"))
    )
    (net (code "52") (name "USB_D+") (class "Default")
      (node (ref "D1") (pin "1") (pinfunction "I/O1_1_1") (pintype "bidirectional"))
      (node (ref "U2") (pin "14") (pinfunction "IO13_14") (pintype "bidirectional"))
    )
    (net (code "53") (name "USB_D-") (class "Default")
      (node (ref "D1") (pin "3") (pinfunction "I/O2_1_3") (pintype "bidirectional"))
      (node (ref "U2") (pin "13") (pinfunction "IO12_13") (pintype "bidirectional"))
    )
    (net (code "54") (name "VBAT") (class "Default")
      (node (ref "C2_BAT") (pin "1") (pinfunction "1_1") (pintype "passive"))
      (node (ref "MCP73831") (pin "3") (pinfunction "VBAT_3") (pintype "power_in"))
      (node (ref "Q1") (pin "3") (pinfunction "D_3") (pintype "bidirectional"))
      (node (ref "TP3") (pin "TP") (pinfunction "TP_TP") (pintype "input"))
      (node (ref "U4") (pin "2") (pinfunction "CELL_2") (pintype "power_in"))
      (node (ref "U4") (pin "3") (pinfunction "VDD_3") (pintype "power_in"))
    )
    (net (code "55") (name "VBUS") (class "Default")
      (node (ref "C1_BAT") (pin "1") (pinfunction "1_1") (pintype "passive"))
      (node (ref "C4_USB") (pin "1") (pinfunction "1_1") (pintype "passive"))
      (node (ref "C5_USB") (pin "1") (pinfunction "1_1") (pintype "passive"))
      (node (ref "CHG_LED") (pin "A") (pinfunction "A_A") (pintype "passive"))
      (node (ref "D1") (pin "5") (pinfunction "VBUS_5") (pintype "bidirectional"))
      (node (ref "D2") (pin "2") (pinfunction "ANODE_2") (pintype "bidirectional"))
      (node (ref "MCP73831") (pin "4") (pinfunction "VIN_4") (pintype "power_in"))
      (node (ref "PFMF.050.1") (pin "2") (pinfunction "2_2") (pintype "passive"))
      (node (ref "Q1") (pin "1") (pinfunction "G_1") (pintype "bidirectional"))
      (node (ref "R1_PWRUSB") (pin "2") (pinfunction "2_2") (pintype "passive"))
      (node (ref "TP14") (pin "TP") (pinfunction "TP_TP") (pintype "input"))
    )
    (net (code "56") (name "VRTC") (class "Default")
      (node (ref "C10_SUPERCAP") (pin "2") (pinfunction "2_2") (pintype "passive"))
      (node (ref "C8") (pin "1") (pinfunction "1_1") (pintype "passive"))
      (node (ref "R_CAPACITOR") (pin "1") (pinfunction "1_1") (pintype "passive"))
      (node (ref "U3") (pin "14") (pinfunction "VBAT_14") (pintype "power_in"))
    )
    (net (code "57") (name "VUSB") (class "Default")
      (node (ref "J2") (pin "A4") (pinfunction "A4_A4") (pintype "bidirectional"))
      (node (ref "J2") (pin "A9") (pinfunction "A9_A9") (pintype "bidirectional"))
      (node (ref "J2") (pin "B4") (pinfunction "B4_B4") (pintype "bidirectional"))
      (node (ref "J2") (pin "B9") (pinfunction "B9_B9") (pintype "bidirectional"))
      (node (ref "PFMF.050.1") (pin "1") (pinfunction "1_1") (pintype "passive"))
    )
    (net (code "58") (name "unconnected-(IC1-NC-Pad4)") (class "Default")
      (node (ref "IC1") (pin "4") (pinfunction "NC_4") (pintype "no_connect"))
    )
    (net (code "59") (name "unconnected-(IC4-NC-Pad4)") (class "Default")
      (node (ref "IC4") (pin "4") (pinfunction "NC_4") (pintype "no_connect"))
    )
    (net (code "60") (name "unconnected-(J1-Pad1)") (class "Default")
      (node (ref "J1") (pin "1") (pinfunction "1_1") (pintype "bidirectional"))
    )
    (net (code "61") (name "unconnected-(J1-Pad6)") (class "Default")
      (node (ref "J1") (pin "6") (pinfunction "6_6") (pintype "bidirectional"))
    )
    (net (code "62") (name "unconnected-(J1-Pad7)") (class "Default")
      (node (ref "J1") (pin "7") (pinfunction "7_7") (pintype "bidirectional"))
    )
    (net (code "63") (name "unconnected-(J2-PadA8)") (class "Default")
      (node (ref "J2") (pin "A8") (pinfunction "A8_A8") (pintype "bidirectional"))
    )
    (net (code "64") (name "unconnected-(J2-PadB8)") (class "Default")
      (node (ref "J2") (pin "B8") (pinfunction "B8_B8") (pintype "bidirectional"))
    )
    (net (code "65") (name "unconnected-(J4-DAT1-PadP8)") (class "Default")
      (node (ref "J4") (pin "P8") (pinfunction "DAT1_P8") (pintype "bidirectional"))
    )
    (net (code "66") (name "unconnected-(J4-DAT2-PadP1)") (class "Default")
      (node (ref "J4") (pin "P1") (pinfunction "DAT2_P1") (pintype "bidirectional"))
    )
    (net (code "67") (name "unconnected-(J4-DETECTION_1-PadS1)") (class "Default")
      (node (ref "J4") (pin "S1") (pinfunction "DETECTION_1_S1") (pintype "bidirectional"))
    )
    (net (code "68") (name "unconnected-(J4-DETECTION_2-PadS2)") (class "Default")
      (node (ref "J4") (pin "S2") (pinfunction "DETECTION_2_S2") (pintype "bidirectional"))
    )
    (net (code "69") (name "unconnected-(U2-NC-Pad22)") (class "Default")
      (node (ref "U2") (pin "22") (pinfunction "NC_22") (pintype "no_connect"))
    )
    (net (code "70") (name "unconnected-(U4-~{ALERT}-Pad5)") (class "Default")
      (node (ref "U4") (pin "5") (pinfunction "~{ALERT}_5") (pintype "output"))
    )
  )
)
